# PW.net
KiCad netlist of a schematic drawn in Altium Designer
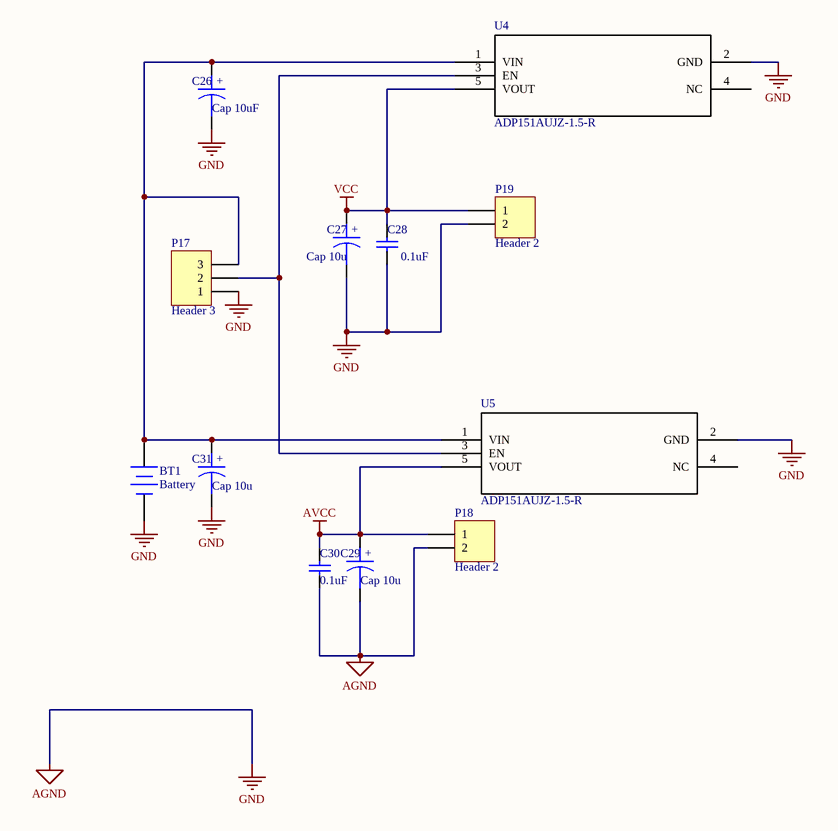
[diagram p0: PW.SchDoc]

(export (version "E")
  (design (tool "Eeschema 10.0.6"))
  (components
    (comp (ref "BT1")
      (value "Battery")
      (footprint "BAT-2")
      (description "Multicell Battery")
      (fields (field (name "PUBLISHER") "Altium Limited"))
      (libsource (lib "Miscellaneous Devices") (part "Battery"))
    )
    (comp (ref "C26")
      (value "Cap 10uF")
      (footprint "C1206")
      (description "Capacitor")
      (libsource (lib "*") (part "CAPACITOR POL"))
    )
    (comp (ref "C27")
      (value "Cap 10u")
      (footprint "C1206")
      (description "Capacitor")
      (libsource (lib "*") (part "CAPACITOR POL"))
    )
    (comp (ref "C28")
      (value "0.1uF")
      (footprint "0603")
      (description "Capacitor")
      (fields (field (name "Comment") "Cap 100nF") (field (name "PUBLISHER") "Altium Limited"))
      (libsource (lib "Miscellaneous Devices") (part "Cap"))
    )
    (comp (ref "C29")
      (value "Cap 10u")
      (footprint "C1206")
      (description "Capacitor")
      (libsource (lib "*") (part "CAPACITOR POL"))
    )
    (comp (ref "C30")
      (value "0.1uF")
      (footprint "0603")
      (description "Capacitor")
      (fields (field (name "Comment") "Cap 100nF") (field (name "PUBLISHER") "Altium Limited"))
      (libsource (lib "Miscellaneous Devices") (part "Cap"))
    )
    (comp (ref "C31")
      (value "Cap 10u")
      (footprint "C1206")
      (description "Capacitor")
      (libsource (lib "*") (part "CAPACITOR POL"))
    )
    (comp (ref "P17")
      (value "Header 3")
      (footprint "HDR1X3")
      (description "Header, 3-Pin")
      (fields (field (name "PUBLISHER") "Altium Limited"))
      (libsource (lib "Miscellaneous Connectors") (part "Header 3"))
    )
    (comp (ref "P18")
      (value "Header 2")
      (footprint "HDR1X2")
      (description "Header, 2-Pin")
      (fields (field (name "PUBLISHER") "Altium Limited"))
      (libsource (lib "Miscellaneous Connectors") (part "Header 2"))
    )
    (comp (ref "P19")
      (value "Header 2")
      (footprint "HDR1X2")
      (description "Header, 2-Pin")
      (fields (field (name "PUBLISHER") "Altium Limited"))
      (libsource (lib "Miscellaneous Connectors") (part "Header 2"))
    )
    (comp (ref "U4")
      (value "ADP151AUJZ-1.5-R")
      (footprint "UJ_5")
      (description "Imported")
      (libsource (lib "2013-07-29_16-10-52") (part "ADP151AUJZ-1.5-R"))
    )
    (comp (ref "U5")
      (value "ADP151AUJZ-1.5-R")
      (footprint "UJ_5")
      (description "Imported")
      (libsource (lib "2013-07-29_16-10-52") (part "ADP151AUJZ-1.5-R"))
    )
  )
  (nets
    (net (code "1") (name "AGND") (class "Default")
      (node (ref "BT1") (pin "2") (pinfunction "-_2") (pintype "passive"))
      (node (ref "C26") (pin "2") (pinfunction "2_2") (pintype "passive"))
      (node (ref "C27") (pin "2") (pinfunction "2_2") (pintype "passive"))
      (node (ref "C28") (pin "1") (pinfunction "1_1") (pintype "passive"))
      (node (ref "C29") (pin "2") (pinfunction "2_2") (pintype "passive"))
      (node (ref "C30") (pin "1") (pinfunction "1_1") (pintype "passive"))
      (node (ref "C31") (pin "2") (pinfunction "2_2") (pintype "passive"))
      (node (ref "P17") (pin "1") (pinfunction "1_1") (pintype "passive"))
      (node (ref "P18") (pin "2") (pinfunction "2_2") (pintype "passive"))
      (node (ref "P19") (pin "2") (pinfunction "2_2") (pintype "passive"))
      (node (ref "U4") (pin "2") (pinfunction "GND_2") (pintype "passive"))
      (node (ref "U5") (pin "2") (pinfunction "GND_2") (pintype "passive"))
    )
    (net (code "2") (name "AVCC") (class "Default")
      (node (ref "C29") (pin "1") (pinfunction "1_1") (pintype "passive"))
      (node (ref "C30") (pin "2") (pinfunction "2_2") (pintype "passive"))
      (node (ref "P18") (pin "1") (pinfunction "1_1") (pintype "passive"))
      (node (ref "U5") (pin "5") (pinfunction "VOUT_5") (pintype "passive"))
    )
    (net (code "3") (name "Net-(BT1-+)") (class "Default")
      (node (ref "BT1") (pin "1") (pinfunction "+_1") (pintype "passive"))
      (node (ref "C26") (pin "1") (pinfunction "1_1") (pintype "passive"))
      (node (ref "C31") (pin "1") (pinfunction "1_1") (pintype "passive"))
      (node (ref "P17") (pin "3") (pinfunction "3_3") (pintype "passive"))
      (node (ref "U4") (pin "1") (pinfunction "VIN_1") (pintype "passive"))
      (node (ref "U5") (pin "1") (pinfunction "VIN_1") (pintype "passive"))
    )
    (net (code "4") (name "Net-(U4-EN)") (class "Default")
      (node (ref "P17") (pin "2") (pinfunction "2_2") (pintype "passive"))
      (node (ref "U4") (pin "3") (pinfunction "EN_3") (pintype "passive"))
      (node (ref "U5") (pin "3") (pinfunction "EN_3") (pintype "passive"))
    )
    (net (code "5") (name "VCC") (class "Default")
      (node (ref "C27") (pin "1") (pinfunction "1_1") (pintype "passive"))
      (node (ref "C28") (pin "2") (pinfunction "2_2") (pintype "passive"))
      (node (ref "P19") (pin "1") (pinfunction "1_1") (pintype "passive"))
      (node (ref "U4") (pin "5") (pinfunction "VOUT_5") (pintype "passive"))
    )
    (net (code "6") (name "unconnected-(U4-NC-Pad4)") (class "Default")
      (node (ref "U4") (pin "4") (pinfunction "NC_4") (pintype "passive"))
    )
    (net (code "7") (name "unconnected-(U5-NC-Pad4)") (class "Default")
      (node (ref "U5") (pin "4") (pinfunction "NC_4") (pintype "passive"))
    )
  )
)
